# GT_Sensor_Theo.net
KiCad netlist of a schematic drawn in EAGLE
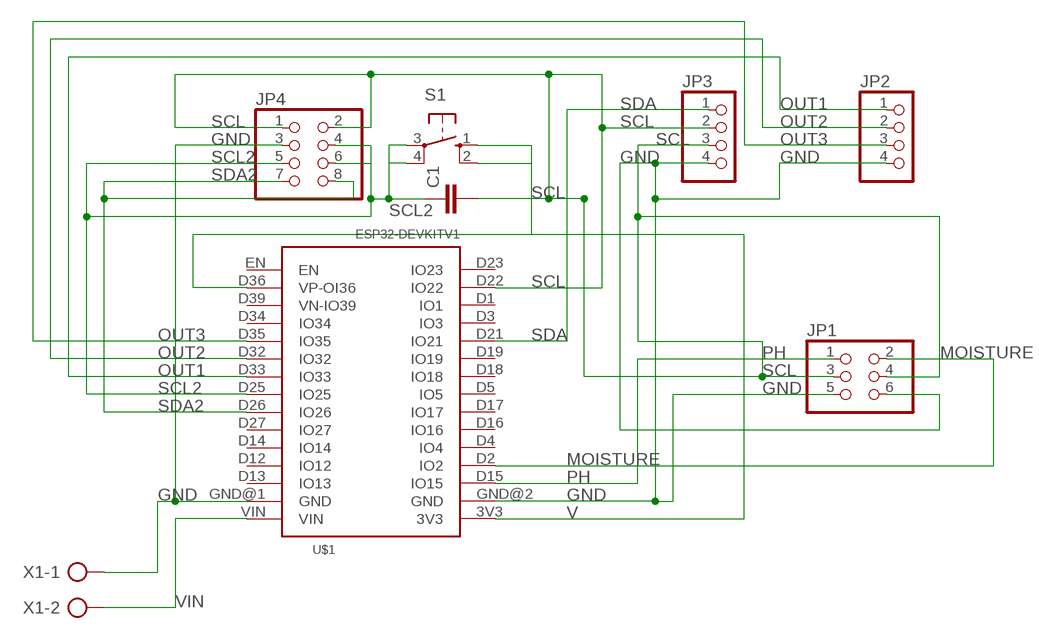
[diagram p0: schematic, sheet 1]

(export (version "E")
  (design (tool "Eeschema 10.0.6"))
  (components
    (comp (ref "C1")
      (value "C-EU050-030X075")
      (footprint "eagle-import:C050-030X075")
      (libsource (lib "eagle-import") (part "C-EU050-030X075"))
    )
    (comp (ref "JP1")
      (value "PINHD-2X3")
      (footprint "eagle-import:2X03")
      (libsource (lib "eagle-import") (part "PINHD-2X3"))
    )
    (comp (ref "JP2")
      (value "PINHD-1X4")
      (footprint "eagle-import:1X04")
      (libsource (lib "eagle-import") (part "PINHD-1X4"))
    )
    (comp (ref "JP3")
      (value "PINHD-1X4")
      (footprint "eagle-import:1X04")
      (libsource (lib "eagle-import") (part "PINHD-1X4"))
    )
    (comp (ref "JP4")
      (value "PINHD-2X4")
      (footprint "eagle-import:2X04")
      (libsource (lib "eagle-import") (part "PINHD-2X4"))
    )
    (comp (ref "S1")
      (value "10-XX")
      (footprint "eagle-import:B3F-10XX")
      (fields (field (name "MPN") "B3F-1000"))
      (libsource (lib "eagle-import") (part "10-XX"))
    )
    (comp (ref "U$1")
      (value "ESP32DEVKITV1")
      (footprint "eagle-import:ESP32-DEVKITV1")
      (libsource (lib "eagle-import") (part "ESP32DEVKITV1"))
    )
    (comp (ref "X1")
      (value "AK300/2")
      (footprint "eagle-import:AK300_2")
      (libsource (lib "eagle-import") (part "AK300/2"))
    )
  )
  (nets
    (net (code "1") (name "/GND") (class "Default")
      (node (ref "JP1") (pin "5") (pinfunction "5_5") (pintype "passive"))
      (node (ref "JP1") (pin "6") (pinfunction "6_6") (pintype "passive"))
      (node (ref "JP2") (pin "4") (pinfunction "4_4") (pintype "passive"))
      (node (ref "JP3") (pin "4") (pinfunction "4_4") (pintype "passive"))
      (node (ref "JP4") (pin "3") (pinfunction "3_3") (pintype "passive"))
      (node (ref "S1") (pin "4") (pinfunction "P1_4") (pintype "passive"))
      (node (ref "U$1") (pin "GND@1") (pinfunction "GND_GND@1") (pintype "bidirectional"))
      (node (ref "U$1") (pin "GND@2") (pinfunction "GND_GND@2") (pintype "bidirectional"))
      (node (ref "X1") (pin "1") (pinfunction "KL_1") (pintype "passive"))
    )
    (net (code "2") (name "/MOISTURE") (class "Default")
      (node (ref "JP1") (pin "2") (pinfunction "2_2") (pintype "passive"))
      (node (ref "U$1") (pin "D2") (pinfunction "IO2_D2") (pintype "bidirectional"))
    )
    (net (code "3") (name "/OUT1") (class "Default")
      (node (ref "JP2") (pin "1") (pinfunction "1_1") (pintype "passive"))
      (node (ref "U$1") (pin "D33") (pinfunction "IO33_D33") (pintype "bidirectional"))
    )
    (net (code "4") (name "/OUT2") (class "Default")
      (node (ref "JP2") (pin "2") (pinfunction "2_2") (pintype "passive"))
      (node (ref "U$1") (pin "D32") (pinfunction "IO32_D32") (pintype "bidirectional"))
    )
    (net (code "5") (name "/OUT3") (class "Default")
      (node (ref "JP2") (pin "3") (pinfunction "3_3") (pintype "passive"))
      (node (ref "U$1") (pin "D35") (pinfunction "IO35_D35") (pintype "bidirectional"))
    )
    (net (code "6") (name "/PH") (class "Default")
      (node (ref "JP1") (pin "1") (pinfunction "1_1") (pintype "passive"))
      (node (ref "U$1") (pin "D15") (pinfunction "IO15_D15") (pintype "bidirectional"))
    )
    (net (code "7") (name "/SCL") (class "Default")
      (node (ref "C1") (pin "2") (pinfunction "2_2") (pintype "passive"))
      (node (ref "JP1") (pin "3") (pinfunction "3_3") (pintype "passive"))
      (node (ref "JP1") (pin "4") (pinfunction "4_4") (pintype "passive"))
      (node (ref "JP3") (pin "2") (pinfunction "2_2") (pintype "passive"))
      (node (ref "JP3") (pin "3") (pinfunction "3_3") (pintype "passive"))
      (node (ref "JP4") (pin "1") (pinfunction "1_1") (pintype "passive"))
      (node (ref "JP4") (pin "2") (pinfunction "2_2") (pintype "passive"))
      (node (ref "U$1") (pin "D22") (pinfunction "IO22_D22") (pintype "bidirectional"))
    )
    (net (code "8") (name "/SCL2") (class "Default")
      (node (ref "C1") (pin "1") (pinfunction "1_1") (pintype "passive"))
      (node (ref "JP4") (pin "4") (pinfunction "4_4") (pintype "passive"))
      (node (ref "JP4") (pin "5") (pinfunction "5_5") (pintype "passive"))
      (node (ref "S1") (pin "3") (pinfunction "P_3") (pintype "passive"))
      (node (ref "U$1") (pin "D25") (pinfunction "IO25_D25") (pintype "bidirectional"))
    )
    (net (code "9") (name "/SDA") (class "Default")
      (node (ref "JP3") (pin "1") (pinfunction "1_1") (pintype "passive"))
      (node (ref "U$1") (pin "D21") (pinfunction "IO21_D21") (pintype "bidirectional"))
    )
    (net (code "10") (name "/SDA2") (class "Default")
      (node (ref "JP4") (pin "7") (pinfunction "7_7") (pintype "passive"))
      (node (ref "JP4") (pin "8") (pinfunction "8_8") (pintype "passive"))
      (node (ref "U$1") (pin "D26") (pinfunction "IO26_D26") (pintype "bidirectional"))
    )
    (net (code "11") (name "/V") (class "Default")
      (node (ref "S1") (pin "1") (pinfunction "S_1") (pintype "passive"))
      (node (ref "S1") (pin "2") (pinfunction "S1_2") (pintype "passive"))
      (node (ref "U$1") (pin "3V3") (pinfunction "3V3_3V3") (pintype "bidirectional"))
      (node (ref "U$1") (pin "D36") (pinfunction "VP-OI36_D36") (pintype "bidirectional"))
    )
    (net (code "12") (name "/VIN") (class "Default")
      (node (ref "U$1") (pin "VIN") (pinfunction "VIN_VIN") (pintype "bidirectional"))
      (node (ref "X1") (pin "2") (pinfunction "KL_2") (pintype "passive"))
    )
    (net (code "13") (name "unconnected-(JP4-Pad6)") (class "Default")
      (node (ref "JP4") (pin "6") (pinfunction "6_6") (pintype "passive"))
    )
    (net (code "14") (name "unconnected-(U$1-IO1-PadD1)") (class "Default")
      (node (ref "U$1") (pin "D1") (pinfunction "IO1_D1") (pintype "bidirectional"))
    )
    (net (code "15") (name "unconnected-(U$1-IO3-PadD3)") (class "Default")
      (node (ref "U$1") (pin "D3") (pinfunction "IO3_D3") (pintype "bidirectional"))
    )
    (net (code "16") (name "unconnected-(U$1-IO4-PadD4)") (class "Default")
      (node (ref "U$1") (pin "D4") (pinfunction "IO4_D4") (pintype "bidirectional"))
    )
    (net (code "17") (name "unconnected-(U$1-IO5-PadD5)") (class "Default")
      (node (ref "U$1") (pin "D5") (pinfunction "IO5_D5") (pintype "bidirectional"))
    )
    (net (code "18") (name "unconnected-(U$1-IO12-PadD12)") (class "Default")
      (node (ref "U$1") (pin "D12") (pinfunction "IO12_D12") (pintype "bidirectional"))
    )
    (net (code "19") (name "unconnected-(U$1-IO13-PadD13)") (class "Default")
      (node (ref "U$1") (pin "D13") (pinfunction "IO13_D13") (pintype "bidirectional"))
    )
    (net (code "20") (name "unconnected-(U$1-IO14-PadD14)") (class "Default")
      (node (ref "U$1") (pin "D14") (pinfunction "IO14_D14") (pintype "bidirectional"))
    )
    (net (code "21") (name "unconnected-(U$1-IO16-PadD16)") (class "Default")
      (node (ref "U$1") (pin "D16") (pinfunction "IO16_D16") (pintype "bidirectional"))
    )
    (net (code "22") (name "unconnected-(U$1-IO17-PadD17)") (class "Default")
      (node (ref "U$1") (pin "D17") (pinfunction "IO17_D17") (pintype "bidirectional"))
    )
    (net (code "23") (name "unconnected-(U$1-IO18-PadD18)") (class "Default")
      (node (ref "U$1") (pin "D18") (pinfunction "IO18_D18") (pintype "bidirectional"))
    )
    (net (code "24") (name "unconnected-(U$1-IO19-PadD19)") (class "Default")
      (node (ref "U$1") (pin "D19") (pinfunction "IO19_D19") (pintype "bidirectional"))
    )
    (net (code "25") (name "unconnected-(U$1-IO23-PadD23)") (class "Default")
      (node (ref "U$1") (pin "D23") (pinfunction "IO23_D23") (pintype "bidirectional"))
    )
    (net (code "26") (name "unconnected-(U$1-IO27-PadD27)") (class "Default")
      (node (ref "U$1") (pin "D27") (pinfunction "IO27_D27") (pintype "bidirectional"))
    )
    (net (code "27") (name "unconnected-(U$1-IO34-PadD34)") (class "Default")
      (node (ref "U$1") (pin "D34") (pinfunction "IO34_D34") (pintype "bidirectional"))
    )
    (net (code "28") (name "unconnected-(U$1-PadEN)") (class "Default")
      (node (ref "U$1") (pin "EN") (pinfunction "EN_EN") (pintype "bidirectional"))
    )
    (net (code "29") (name "unconnected-(U$1-VN-IO39-PadD39)") (class "Default")
      (node (ref "U$1") (pin "D39") (pinfunction "VN-IO39_D39") (pintype "bidirectional"))
    )
  )
)
